# RP2350.net
KiCad netlist of a schematic drawn in Altium Designer
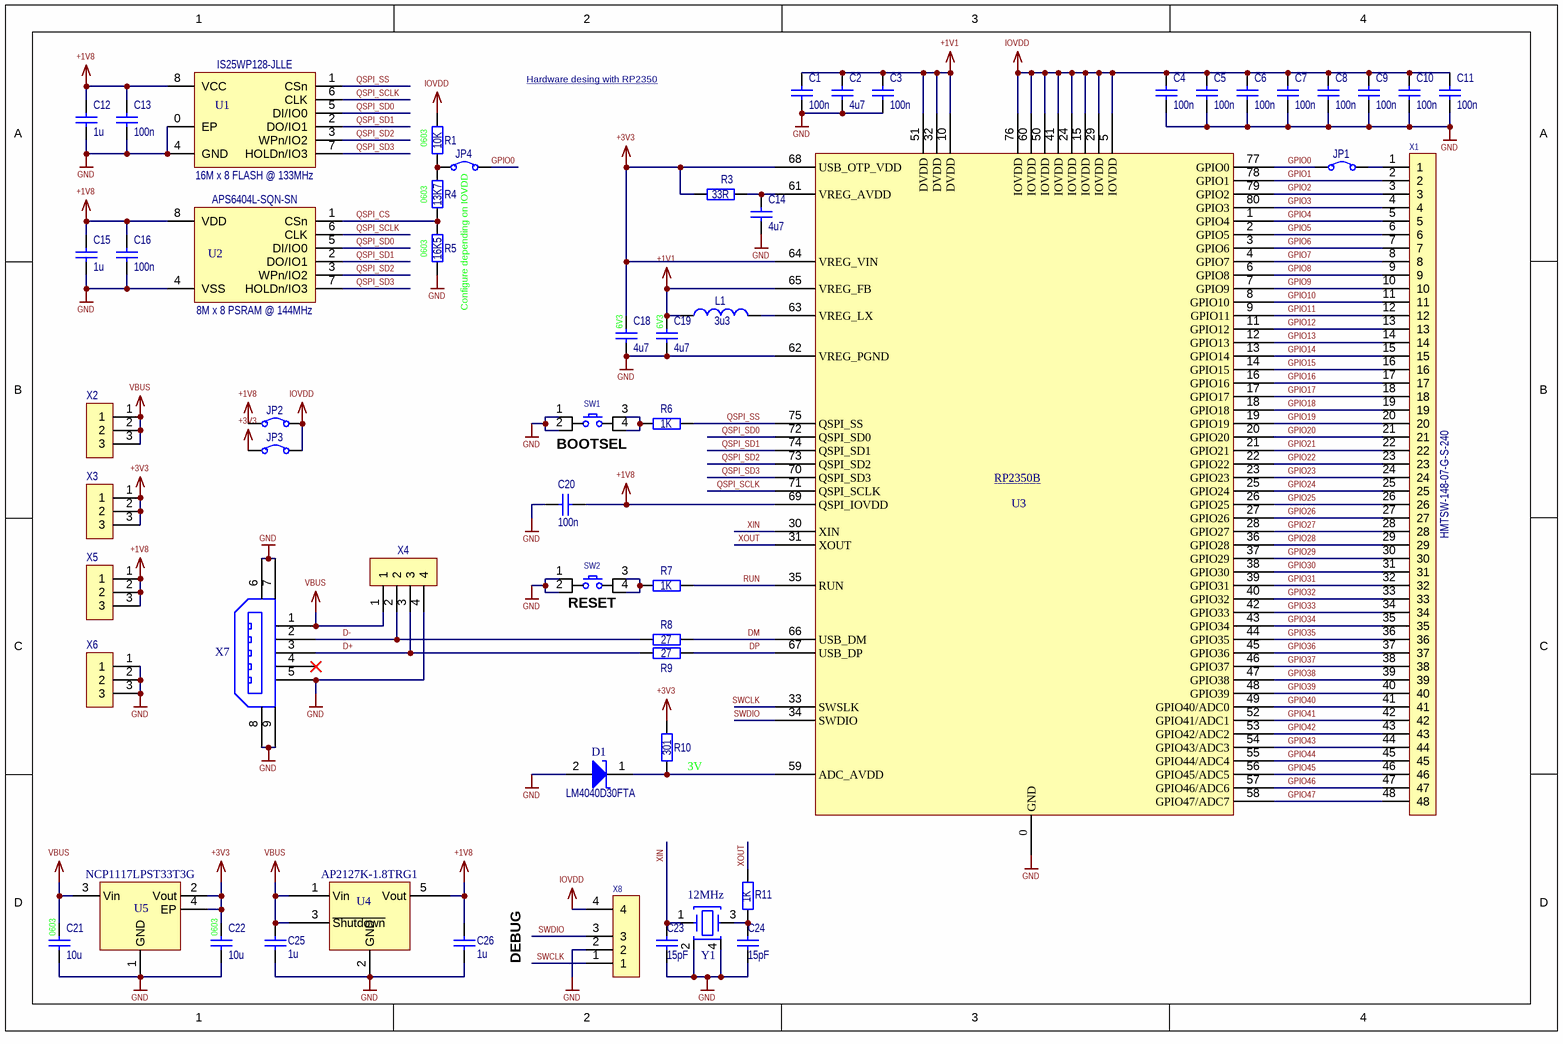
[diagram p0: RP2350.SchDoc]

(export (version "E")
  (design (tool "Eeschema 10.0.6"))
  (components
    (comp (ref "C1")
      (value "100n")
      (footprint "CAPC0402")
      (description "Capacitor; Ceramic; 100n; 2; 10V; X7R; 5%; -55°C ~ 125°C")
      (fields (field (name "Comment") "C0402C104J8RACTU"))
      (libsource (lib "Capacitors") (part "100n_0402_10V_X7R_5%"))
    )
    (comp (ref "C2")
      (value "4u7")
      (footprint "CAPC0402")
      (description "Capacitor; Ceramic; 4.7u; 0402; 10V; X5R; 10%; -55°C ~ 85°C")
      (fields
        (field (name "MANUFACTURER") "Samsung Electro-Mechanics")
        (field (name "MANUFACTURER PART NUMBER") "CL05A475KP5NRNC")
      )
      (libsource (lib "Capacitors") (part "4u7_0402_10V_X5R_10%"))
    )
    (comp (ref "C3")
      (value "100n")
      (footprint "CAPC0402")
      (description "Capacitor; Ceramic; 100n; 0402; 10V; X7R; 5%; -55°C ~ 125°C")
      (fields (field (name "Comment") "C0402C104J8RACTU"))
      (libsource (lib "Capacitors") (part "100n_0402_10V_X7R_5%"))
    )
    (comp (ref "C4")
      (value "100n")
      (footprint "CAPC0402")
      (description "Capacitor; Ceramic; 100n; 0402; 10V; X7R; 5%; -55°C ~ 125°C")
      (fields (field (name "Comment") "C0402C104J8RACTU"))
      (libsource (lib "Capacitors") (part "100n_0402_10V_X7R_5%"))
    )
    (comp (ref "C5")
      (value "100n")
      (footprint "CAPC0402")
      (description "Capacitor; Ceramic; 100n; 0402; 10V; X7R; 5%; -55°C ~ 125°C")
      (fields (field (name "Comment") "C0402C104J8RACTU"))
      (libsource (lib "Capacitors") (part "100n_0402_10V_X7R_5%"))
    )
    (comp (ref "C6")
      (value "100n")
      (footprint "CAPC0402")
      (description "Capacitor; Ceramic; 100n; 0402; 10V; X7R; 5%; -55°C ~ 125°C")
      (fields (field (name "Comment") "C0402C104J8RACTU"))
      (libsource (lib "Capacitors") (part "100n_0402_10V_X7R_5%"))
    )
    (comp (ref "C7")
      (value "100n")
      (footprint "CAPC0402")
      (description "Capacitor; Ceramic; 100n; 0402; 10V; X7R; 5%; -55°C ~ 125°C")
      (fields (field (name "Comment") "C0402C104J8RACTU"))
      (libsource (lib "Capacitors") (part "100n_0402_10V_X7R_5%"))
    )
    (comp (ref "C8")
      (value "100n")
      (footprint "CAPC0402")
      (description "Capacitor; Ceramic; 100n; 0402; 10V; X7R; 5%; -55°C ~ 125°C")
      (fields (field (name "Comment") "C0402C104J8RACTU"))
      (libsource (lib "Capacitors") (part "100n_0402_10V_X7R_5%"))
    )
    (comp (ref "C9")
      (value "100n")
      (footprint "CAPC0402")
      (description "Capacitor; Ceramic; 100n; 0402; 10V; X7R; 5%; -55°C ~ 125°C")
      (fields (field (name "Comment") "C0402C104J8RACTU"))
      (libsource (lib "Capacitors") (part "100n_0402_10V_X7R_5%"))
    )
    (comp (ref "C10")
      (value "100n")
      (footprint "CAPC0402")
      (description "Capacitor; Ceramic; 100n; 0402; 10V; X7R; 5%; -55°C ~ 125°C")
      (fields (field (name "Comment") "C0402C104J8RACTU"))
      (libsource (lib "Capacitors") (part "100n_0402_10V_X7R_5%"))
    )
    (comp (ref "C11")
      (value "100n")
      (footprint "CAPC0402")
      (description "Capacitor; Ceramic; 100n; 0402; 10V; X7R; 5%; -55°C ~ 125°C")
      (fields (field (name "Comment") "C0402C104J8RACTU"))
      (libsource (lib "Capacitors") (part "100n_0402_10V_X7R_5%"))
    )
    (comp (ref "C12")
      (value "1u")
      (footprint "CAPC0402")
      (description "Capacitor; Ceramic; 1u; 0402; 10V; X5R; 10%; -55°C ~ 85°C")
      (fields
        (field (name "MANUFACTURER") "Samsung Electro-Mechanics")
        (field (name "MANUFACTURER PART NUMBER") "CL05A105KP5NNNC")
      )
      (libsource (lib "Capacitors") (part "1u_0402_10V_X5R_10%"))
    )
    (comp (ref "C13")
      (value "100n")
      (footprint "CAPC0402")
      (description "Capacitor; Ceramic; 100n; 0402; 10V; X7R; 5%; -55°C ~ 125°C")
      (fields (field (name "Comment") "C0402C104J8RACTU"))
      (libsource (lib "Capacitors") (part "100n_0402_10V_X7R_5%"))
    )
    (comp (ref "C14")
      (value "4u7")
      (footprint "CAPC0402")
      (description "Capacitor; Ceramic; 4.7u; 0402; 10V; X5R; 10%; -55°C ~ 85°C")
      (fields
        (field (name "MANUFACTURER") "Samsung Electro-Mechanics")
        (field (name "MANUFACTURER PART NUMBER") "CL05A475KP5NRNC")
      )
      (libsource (lib "Capacitors") (part "4u7_0402_10V_X5R_10%"))
    )
    (comp (ref "C15")
      (value "1u")
      (footprint "CAPC0402")
      (description "Capacitor; Ceramic; 1u; 0402; 10V; X5R; 10%; -55°C ~ 85°C")
      (fields
        (field (name "MANUFACTURER") "Samsung Electro-Mechanics")
        (field (name "MANUFACTURER PART NUMBER") "CL05A105KP5NNNC")
      )
      (libsource (lib "Capacitors") (part "1u_0402_10V_X5R_10%"))
    )
    (comp (ref "C16")
      (value "100n")
      (footprint "CAPC0402")
      (description "Capacitor; Ceramic; 100n; 0402; 10V; X7R; 5%; -55°C ~ 125°C")
      (fields (field (name "Comment") "C0402C104J8RACTU"))
      (libsource (lib "Capacitors") (part "100n_0402_10V_X7R_5%"))
    )
    (comp (ref "C18")
      (value "6V3")
      (footprint "CAPC0603")
      (description "Capacitor; Ceramic; 4.7u; 0603; 6.3V; X7S; 10%; -55°C ~ 125°C")
      (fields
        (field (name "MANUFACTURER") "Murata Electronics")
        (field (name "MANUFACTURER PART NUMBER") "GCJ188C70J475KE02D")
        (field (name "ALTIUM_VALUE") "4u7")
      )
      (libsource (lib "symbols") (part "4u7_0603_6V3_X7S_10%"))
    )
    (comp (ref "C19")
      (value "6V3")
      (footprint "CAPC0603")
      (description "Capacitor; Ceramic; 4.7u; 0603; 6.3V; X7S; 10%; -55°C ~ 125°C")
      (fields
        (field (name "MANUFACTURER") "Murata Electronics")
        (field (name "MANUFACTURER PART NUMBER") "GCJ188C70J475KE02D")
        (field (name "ALTIUM_VALUE") "4u7")
      )
      (libsource (lib "symbols") (part "4u7_0603_6V3_X7S_10%"))
    )
    (comp (ref "C20")
      (value "100n")
      (footprint "CAPC0402")
      (description "Capacitor; Ceramic; 100n; 0402; 10V; X7R; 5%; -55°C ~ 125°C")
      (fields (field (name "Comment") "C0402C104J8RACTU"))
      (libsource (lib "Capacitors") (part "100n_0402_10V_X7R_5%"))
    )
    (comp (ref "C21")
      (value "0603")
      (footprint "CAPC0603")
      (description "Capacitor; Ceramic; 10u; 0603; 16V; X5R; 10%; -55°C ~ 85°C")
      (fields (field (name "ALTIUM_VALUE") "10u"))
      (libsource (lib "Capacitors") (part "10u_0603_16V_X5R_10%"))
    )
    (comp (ref "C22")
      (value "0603")
      (footprint "CAPC0603")
      (description "Capacitor; Ceramic; 10u; 0603; 16V; X5R; 10%; -55°C ~ 85°C")
      (fields (field (name "ALTIUM_VALUE") "10u"))
      (libsource (lib "Capacitors") (part "10u_0603_16V_X5R_10%"))
    )
    (comp (ref "C23")
      (value "15pF")
      (footprint "CAPC0402")
      (description "Capacitor; Ceramic; 15p; 0402; 25V; C0G/NP0; +/-5%; -55°C ~ 125°C")
      (fields
        (field (name "MANUFACTURER") "YAGEO")
        (field (name "MANUFACTURER PART NUMBER") "CC0402JRNPO8BN150")
      )
      (libsource (lib "symbols") (part "15p_0402_25V_C0G/NP0_5%"))
    )
    (comp (ref "C24")
      (value "15pF")
      (footprint "CAPC0402")
      (description "Capacitor; Ceramic; 15p; 0402; 25V; C0G/NP0; +/-5%; -55°C ~ 125°C")
      (fields
        (field (name "MANUFACTURER") "YAGEO")
        (field (name "MANUFACTURER PART NUMBER") "CC0402JRNPO8BN150")
      )
      (libsource (lib "symbols") (part "15p_0402_25V_C0G/NP0_5%"))
    )
    (comp (ref "C25")
      (value "1u")
      (footprint "CAPC0402")
      (description "Capacitor; Ceramic; 1u; 0402; 10V; X5R; 10%; -55°C ~ 85°C")
      (fields
        (field (name "MANUFACTURER") "Samsung Electro-Mechanics")
        (field (name "MANUFACTURER PART NUMBER") "CL05A105KP5NNNC")
      )
      (libsource (lib "Capacitors") (part "1u_0402_10V_X5R_10%"))
    )
    (comp (ref "C26")
      (value "1u")
      (footprint "CAPC0402")
      (description "Capacitor; Ceramic; 1u; 0402; 10V; X5R; 10%; -55°C ~ 85°C")
      (fields
        (field (name "MANUFACTURER") "Samsung Electro-Mechanics")
        (field (name "MANUFACTURER PART NUMBER") "CL05A105KP5NNNC")
      )
      (libsource (lib "Capacitors") (part "1u_0402_10V_X5R_10%"))
    )
    (comp (ref "D1")
      (value "LM4040D30FTA")
      (footprint "SOT23-3")
      (description "Shunt Voltage Reference IC Fixed 3V ±1% 15 mA SOT-23-3")
      (fields (field (name "MANUFACTURER") "Diodes Incorporated") (field (name "ALTIUM_VALUE") "3V"))
      (libsource (lib "symbols") (part "LM4040D30FTA"))
    )
    (comp (ref "JP1")
      (value "5110 Keystone")
      (footprint "JumperSMD_0603")
      (description "Jumper; Chip; 0R; 0603; 500mW")
      (fields (field (name "MANUFACTURER") "Keystone") (field (name "MANUFACTURER PART NUMBER") "5110"))
      (libsource (lib "Jumpers") (part "JMP_0R_0603"))
    )
    (comp (ref "JP2")
      (value "5110 Keystone")
      (footprint "JumperSMD_0603")
      (description "Jumper; Chip; 0R; 0603; 500mW")
      (fields (field (name "MANUFACTURER") "Keystone") (field (name "MANUFACTURER PART NUMBER") "5110"))
      (libsource (lib "Jumpers") (part "JMP_0R_0603"))
    )
    (comp (ref "JP3")
      (value "5110 Keystone")
      (footprint "JumperSMD_0603")
      (description "Jumper; Chip; 0R; 0603; 500mW")
      (fields (field (name "MANUFACTURER") "Keystone") (field (name "MANUFACTURER PART NUMBER") "5110"))
      (libsource (lib "Jumpers") (part "JMP_0R_0603"))
    )
    (comp (ref "JP4")
      (value "5110 Keystone")
      (footprint "JumperSMD_0603")
      (description "Jumper; Chip; 0R; 0603; 500mW")
      (fields (field (name "MANUFACTURER") "Keystone") (field (name "MANUFACTURER PART NUMBER") "5110"))
      (libsource (lib "Jumpers") (part "JMP_0R_0603"))
    )
    (comp (ref "L1")
      (value "3u3")
      (footprint "IND_0806")
      (description "3.3 µH Shielded Inductor 1.4 A 225mOhm Max 0806")
      (fields
        (field (name "MANUFACTURER") "Bourns Inc.")
        (field (name "MANUFACTURER PART NUMBER") "SRP2010DPA-3R3M")
      )
      (libsource (lib "Inductances") (part "IND_3u3_2X1.6mm_1.4A_20%"))
    )
    (comp (ref "R1")
      (value "0603")
      (footprint "RESC0603")
      (description "Resistor; Chip; 10k; 0603; 75V; 1%; 100ppm; 100mW; -55°C ~ 155°C")
      (fields (field (name "ALTIUM_VALUE") "10K"))
      (libsource (lib "Resistors") (part "10K_0603_100mW_1%_100ppm"))
    )
    (comp (ref "R3")
      (value "33R")
      (footprint "RESC0402")
      (description "Resistor; Chip; 33R; 0402; 50V; 1%; 100ppm; 63mW; -55°C ~ 155°C")
      (fields
        (field (name "MANUFACTURER") "Yageo")
        (field (name "MANUFACTURER PART NUMBER") "RC0402FR-0733RL")
      )
      (libsource (lib "Resistors") (part "33R_0402_63mW_1%_100ppm"))
    )
    (comp (ref "R4")
      (value "0603")
      (footprint "RESC0603")
      (description "Resistor; Chip; 13K7; 0603; 0.1%; 25ppm; 100mW; -55°C ~ 155°C")
      (fields
        (field (name "MANUFACTURER") "YAGEO")
        (field (name "MANUFACTURER PART NUMBER") "RT0603BRD0713K7L")
        (field (name "ALTIUM_VALUE") "13K7")
      )
      (libsource (lib "symbols") (part "13K7_0603_100mW_0.1%_25ppm"))
    )
    (comp (ref "R5")
      (value "0603")
      (footprint "RESC0603")
      (description "Resistor; Chip; 16K5; 0603; 0.1%; 25ppm; 100mW; -55°C ~ 155°C")
      (fields
        (field (name "MANUFACTURER") "YAGEO")
        (field (name "MANUFACTURER PART NUMBER") "RT0603BRD0716K5L")
        (field (name "ALTIUM_VALUE") "16K5")
      )
      (libsource (lib "symbols") (part "16K5_0603_100mW_0.1%_25ppm"))
    )
    (comp (ref "R6")
      (value "1K")
      (footprint "RESC0402")
      (description "Resistor; Chip; 1k; 0402; 50V; 1%; 100ppm; 63mW; -55°C ~ 155°C")
      (fields
        (field (name "MANUFACTURER") "Yageo")
        (field (name "MANUFACTURER PART NUMBER") "RC0402FR-071KL")
      )
      (libsource (lib "") (part "1K_0402_63mW_1%_100ppm_1"))
    )
    (comp (ref "R7")
      (value "1K")
      (footprint "RESC0402")
      (description "Resistor; Chip; 1k; 0402; 50V; 1%; 100ppm; 63mW; -55°C ~ 155°C")
      (fields
        (field (name "MANUFACTURER") "Yageo")
        (field (name "MANUFACTURER PART NUMBER") "RC0402FR-071KL")
      )
      (libsource (lib "") (part "1K_0402_63mW_1%_100ppm_1"))
    )
    (comp (ref "R8")
      (value "27")
      (footprint "RESC0402")
      (description "Resistor; Chip; 27Ohm; 0402; 1%; 100ppm; 63mW; -55°C ~ 155°C")
      (fields
        (field (name "MANUFACTURER") "YAGEO")
        (field (name "MANUFACTURER PART NUMBER") "RC0402FR-0727RL")
      )
      (libsource (lib "symbols") (part "27R_0402_63mW_1%_100ppm"))
    )
    (comp (ref "R9")
      (value "27")
      (footprint "RESC0402")
      (description "Resistor; Chip; 27Ohm; 0402; 1%; 100ppm; 63mW; -55°C ~ 155°C")
      (fields
        (field (name "MANUFACTURER") "YAGEO")
        (field (name "MANUFACTURER PART NUMBER") "RC0402FR-0727RL")
      )
      (libsource (lib "symbols") (part "27R_0402_63mW_1%_100ppm"))
    )
    (comp (ref "R10")
      (value "301")
      (footprint "RESC0402")
      (description "Resistor; Chip; 301R; 0402; 1%; 100ppm; 63mW; -55°C ~ 155°C")
      (fields
        (field (name "MANUFACTURER") "YAGEO")
        (field (name "MANUFACTURER PART NUMBER") "RC0402FR-07301RL")
      )
      (libsource (lib "symbols") (part "301R_0402_63mW_1%_100ppm"))
    )
    (comp (ref "R11")
      (value "1K")
      (footprint "RESC0402")
      (description "Resistor; Chip; 1k; 0402; 50V; 1%; 100ppm; 63mW; -55°C ~ 155°C")
      (fields
        (field (name "MANUFACTURER") "Yageo")
        (field (name "MANUFACTURER PART NUMBER") "RC0402FR-071KL")
      )
      (libsource (lib "Resistors") (part "1K_0402_63mW_1%_100ppm"))
    )
    (comp (ref "SW1")
      (value "434133025816")
      (footprint "434133025816")
      (description "SWITCH TACTILE SPST-NO 0.05A 16V")
      (fields (field (name "MANUFACTURER") "Würth Elektronik"))
      (libsource (lib "symbols") (part "434133025816"))
    )
    (comp (ref "SW2")
      (value "434133025816")
      (footprint "434133025816")
      (description "SWITCH TACTILE SPST-NO 0.05A 16V")
      (fields (field (name "MANUFACTURER") "Würth Elektronik"))
      (libsource (lib "symbols") (part "434133025816"))
    )
    (comp (ref "U1")
      (value "16M x 8 FLASH @ 133MHz")
      (footprint "WSON8-6x8")
      (description "IC FLASH 128MBIT SPI/QUAD 8WSON")
      (fields
        (field (name "MANUFACTURER") "ISSI, Integrated Silicon Solution Inc")
        (field (name "MANUFACTURER PART NUMBER") "IS25WP128-JLLE")
        (field (name "Comment") "IS25WP128-JLLE")
      )
      (libsource (lib "symbols") (part "IS25WP128-JLLE"))
    )
    (comp (ref "U2")
      (value "8M x 8 PSRAM @ 144MHz")
      (footprint "SOP-8L (150)")
      (description "IC PSRAM 64MBIT QSPI SOP-8L")
      (fields
        (field (name "MANUFACTURER") "AP Memory")
        (field (name "MANUFACTURER PART NUMBER") "APS6404L-SQN-SN")
        (field (name "Comment") "APS6404L-SQN-SN")
      )
      (libsource (lib "symbols") (part "APS6404L-SQN-SN"))
    )
    (comp (ref "U3")
      (value "RP2350B")
      (footprint "QFN-80")
      (description "IC MCU 32BIT EXT MEM 80QFN")
      (libsource (lib "symbols") (part "RP2350B"))
    )
    (comp (ref "U4")
      (value "AP2127K-1.8TRG1")
      (footprint "SOT23-5")
      (description "IC REG LINEAR 1.8V 300MA SOT23-5")
      (fields
        (field (name "MANUFACTURER") "Diodes Incorporated")
        (field (name "MANUFACTURER PART NUMBER") "AP2127K-1.8TRG1")
      )
      (libsource (lib "symbols") (part "AP2127K-1.8TRG1"))
    )
    (comp (ref "U5")
      (value "NCP1117LPST33T3G")
      (footprint "SOT-232-4")
      (description "IC REG LINEAR 3.3V 1A SOT223")
      (fields (field (name "MANUFACTURER") "onsemi"))
      (libsource (lib "symbols") (part "NCP1117LPST33T3G"))
    )
    (comp (ref "X1")
      (value "HMTSW-148-07-G-S-240")
      (footprint "HDR_TH_1X48_M_00")
      (description "Header; 1x48 pins; Male; Straight; Pitch 2.54mm; Samtec HMTSW Series")
      (libsource (lib "symbols") (part "HDR_TH_1X48_M_00"))
    )
    (comp (ref "X2")
      (value "825433-3")
      (footprint "HDR_TH_1X3_M_00")
      (description "Header; 1x3 pins; Male; Straight; Pitch 2.54mm")
      (fields
        (field (name "MANUFACTURER") "TE Connectivity")
        (field (name "MANUFACTURER PART NUMBER") "825433-2")
      )
      (libsource (lib "Connections") (part "HDR_TH_1X3_M_00"))
    )
    (comp (ref "X3")
      (value "825433-3")
      (footprint "HDR_TH_1X3_M_00")
      (description "Header; 1x3 pins; Male; Straight; Pitch 2.54mm")
      (fields
        (field (name "MANUFACTURER") "TE Connectivity")
        (field (name "MANUFACTURER PART NUMBER") "825433-2")
      )
      (libsource (lib "Connections") (part "HDR_TH_1X3_M_00"))
    )
    (comp (ref "X4")
      (value "HMTSW-104-07-G-S-240")
      (footprint "HDR_TH_1X4_M_00")
      (description "Header; 1x4 pins; Male; Straight; Pitch 2.54mm; Samtec HMTSW Series")
      (libsource (lib "symbols") (part "HDR_TH_1X4_M_00"))
    )
    (comp (ref "X5")
      (value "825433-3")
      (footprint "HDR_TH_1X3_M_00")
      (description "Header; 1x3 pins; Male; Straight; Pitch 2.54mm")
      (fields
        (field (name "MANUFACTURER") "TE Connectivity")
        (field (name "MANUFACTURER PART NUMBER") "825433-2")
      )
      (libsource (lib "Connections") (part "HDR_TH_1X3_M_00"))
    )
    (comp (ref "X6")
      (value "825433-3")
      (footprint "HDR_TH_1X3_M_00")
      (description "Header; 1x3 pins; Male; Straight; Pitch 2.54mm")
      (fields
        (field (name "MANUFACTURER") "TE Connectivity")
        (field (name "MANUFACTURER PART NUMBER") "825433-2")
      )
      (libsource (lib "Connections") (part "HDR_TH_1X3_M_00"))
    )
    (comp (ref "X7")
      (value "1734327-1")
      (footprint "1734327-1")
      (description "USB - mini A USB 2.0 Receptacle Connector 5 Position Surface Mount, Right Angle")
      (fields (field (name "MANUFACTURER") "TE Connectivity AMP Connectors"))
      (libsource (lib "symbols") (part "1734327-1"))
    )
    (comp (ref "X8")
      (value "HMTSW-106-07-G-S-240")
      (footprint "HDR_TH_1X3+0+1_M_00")
      (description "Header; 1x5 pins (with key); Male; Straight; Pitch 2.54mm; Samtec HMTSW Series")
      (fields
        (field (name "MANUFACTURER") "Samtec Inc.")
        (field (name "MANUFACTURER PART NUMBER") "HMTSW-105-07-G-S-240")
      )
      (libsource (lib "symbols") (part "HDR_TH_1X3+1_M_00"))
    )
    (comp (ref "Y1")
      (value "12MHz")
      (footprint "ABM8")
      (description "Christal; SMD; 12 MHz ±30ppm; 10pF/50Ohm")
      (fields
        (field (name "MANUFACTURER") "Abracon LLC")
        (field (name "MANUFACTURER PART NUMBER") "ABM8-272-T3")
      )
      (libsource (lib "symbols") (part "ABM8-272-T3"))
    )
  )
  (nets
    (net (code "1") (name "+1V1") (class "Default")
      (node (ref "C1") (pin "2") (pinfunction "2_2") (pintype "passive"))
      (node (ref "C19") (pin "2") (pinfunction "2_2") (pintype "passive"))
      (node (ref "C2") (pin "2") (pinfunction "2_2") (pintype "passive"))
      (node (ref "C3") (pin "2") (pinfunction "2_2") (pintype "passive"))
      (node (ref "L1") (pin "1") (pinfunction "1_1") (pintype "passive"))
      (node (ref "U3") (pin "10") (pinfunction "DVDD_10") (pintype "passive"))
      (node (ref "U3") (pin "32") (pinfunction "DVDD_32") (pintype "passive"))
      (node (ref "U3") (pin "51") (pinfunction "DVDD_51") (pintype "passive"))
      (node (ref "U3") (pin "65") (pinfunction "VREG_FB_65") (pintype "passive"))
    )
    (net (code "2") (name "+1V8") (class "Default")
      (node (ref "C12") (pin "1") (pinfunction "1_1") (pintype "passive"))
      (node (ref "C13") (pin "2") (pinfunction "2_2") (pintype "passive"))
      (node (ref "C15") (pin "1") (pinfunction "1_1") (pintype "passive"))
      (node (ref "C16") (pin "2") (pinfunction "2_2") (pintype "passive"))
      (node (ref "C20") (pin "2") (pinfunction "2_2") (pintype "passive"))
      (node (ref "C26") (pin "1") (pinfunction "1_1") (pintype "passive"))
      (node (ref "JP2") (pin "1") (pinfunction "1_1") (pintype "passive"))
      (node (ref "U1") (pin "8") (pinfunction "VCC_8") (pintype "passive"))
      (node (ref "U2") (pin "8") (pinfunction "VDD_8") (pintype "passive"))
      (node (ref "U3") (pin "69") (pinfunction "QSPI_IOVDD_69") (pintype "passive"))
      (node (ref "U4") (pin "5") (pinfunction "Vout_5") (pintype "passive"))
      (node (ref "X5") (pin "1") (pinfunction "1_1") (pintype "passive"))
      (node (ref "X5") (pin "2") (pinfunction "2_2") (pintype "passive"))
      (node (ref "X5") (pin "3") (pinfunction "3_3") (pintype "passive"))
    )
    (net (code "3") (name "+3V3") (class "Default")
      (node (ref "C18") (pin "2") (pinfunction "2_2") (pintype "passive"))
      (node (ref "C22") (pin "2") (pinfunction "2_2") (pintype "passive"))
      (node (ref "JP3") (pin "1") (pinfunction "1_1") (pintype "passive"))
      (node (ref "R10") (pin "2") (pinfunction "2_2") (pintype "passive"))
      (node (ref "R3") (pin "1") (pinfunction "1_1") (pintype "passive"))
      (node (ref "U3") (pin "64") (pinfunction "VREG_VIN_64") (pintype "passive"))
      (node (ref "U3") (pin "68") (pinfunction "USB_OTP_VDD_68") (pintype "passive"))
      (node (ref "U5") (pin "2") (pinfunction "Vout_2") (pintype "passive"))
      (node (ref "U5") (pin "4") (pinfunction "EP_4") (pintype "passive"))
      (node (ref "X3") (pin "1") (pinfunction "1_1") (pintype "passive"))
      (node (ref "X3") (pin "2") (pinfunction "2_2") (pintype "passive"))
      (node (ref "X3") (pin "3") (pinfunction "3_3") (pintype "passive"))
    )
    (net (code "4") (name "/D+") (class "Default")
      (node (ref "R9") (pin "1") (pinfunction "1_1") (pintype "passive"))
      (node (ref "X4") (pin "3") (pinfunction "3_3") (pintype "passive"))
      (node (ref "X7") (pin "3") (pinfunction "3_3") (pintype "passive"))
    )
    (net (code "5") (name "/D-") (class "Default")
      (node (ref "R8") (pin "1") (pinfunction "1_1") (pintype "passive"))
      (node (ref "X4") (pin "2") (pinfunction "2_2") (pintype "passive"))
      (node (ref "X7") (pin "2") (pinfunction "2_2") (pintype "passive"))
    )
    (net (code "6") (name "/DM") (class "Default")
      (node (ref "R8") (pin "2") (pinfunction "2_2") (pintype "passive"))
      (node (ref "U3") (pin "66") (pinfunction "USB_DM_66") (pintype "passive"))
    )
    (net (code "7") (name "/DP") (class "Default")
      (node (ref "R9") (pin "2") (pinfunction "2_2") (pintype "passive"))
      (node (ref "U3") (pin "67") (pinfunction "USB_DP_67") (pintype "passive"))
    )
    (net (code "8") (name "/GPIO0") (class "Default")
      (node (ref "JP1") (pin "1") (pinfunction "1_1") (pintype "passive"))
      (node (ref "JP4") (pin "2") (pinfunction "2_2") (pintype "passive"))
      (node (ref "U3") (pin "77") (pinfunction "GPIO0_77") (pintype "passive"))
    )
    (net (code "9") (name "/GPIO1") (class "Default")
      (node (ref "U3") (pin "78") (pinfunction "GPIO1_78") (pintype "passive"))
      (node (ref "X1") (pin "2") (pinfunction "2_2") (pintype "passive"))
    )
    (net (code "10") (name "/GPIO2") (class "Default")
      (node (ref "U3") (pin "79") (pinfunction "GPIO2_79") (pintype "passive"))
      (node (ref "X1") (pin "3") (pinfunction "3_3") (pintype "passive"))
    )
    (net (code "11") (name "/GPIO3") (class "Default")
      (node (ref "U3") (pin "80") (pinfunction "GPIO3_80") (pintype "passive"))
      (node (ref "X1") (pin "4") (pinfunction "4_4") (pintype "passive"))
    )
    (net (code "12") (name "/GPIO4") (class "Default")
      (node (ref "U3") (pin "1") (pinfunction "GPIO4_1") (pintype "passive"))
      (node (ref "X1") (pin "5") (pinfunction "5_5") (pintype "passive"))
    )
    (net (code "13") (name "/GPIO5") (class "Default")
      (node (ref "U3") (pin "2") (pinfunction "GPIO5_2") (pintype "passive"))
      (node (ref "X1") (pin "6") (pinfunction "6_6") (pintype "passive"))
    )
    (net (code "14") (name "/GPIO6") (class "Default")
      (node (ref "U3") (pin "3") (pinfunction "GPIO6_3") (pintype "passive"))
      (node (ref "X1") (pin "7") (pinfunction "7_7") (pintype "passive"))
    )
    (net (code "15") (name "/GPIO7") (class "Default")
      (node (ref "U3") (pin "4") (pinfunction "GPIO7_4") (pintype "passive"))
      (node (ref "X1") (pin "8") (pinfunction "8_8") (pintype "passive"))
    )
    (net (code "16") (name "/GPIO8") (class "Default")
      (node (ref "U3") (pin "6") (pinfunction "GPIO8_6") (pintype "passive"))
      (node (ref "X1") (pin "9") (pinfunction "9_9") (pintype "passive"))
    )
    (net (code "17") (name "/GPIO9") (class "Default")
      (node (ref "U3") (pin "7") (pinfunction "GPIO9_7") (pintype "passive"))
      (node (ref "X1") (pin "10") (pinfunction "10_10") (pintype "passive"))
    )
    (net (code "18") (name "/GPIO10") (class "Default")
      (node (ref "U3") (pin "8") (pinfunction "GPIO10_8") (pintype "passive"))
      (node (ref "X1") (pin "11") (pinfunction "11_11") (pintype "passive"))
    )
    (net (code "19") (name "/GPIO11") (class "Default")
      (node (ref "U3") (pin "9") (pinfunction "GPIO11_9") (pintype "passive"))
      (node (ref "X1") (pin "12") (pinfunction "12_12") (pintype "passive"))
    )
    (net (code "20") (name "/GPIO12") (class "Default")
      (node (ref "U3") (pin "11") (pinfunction "GPIO12_11") (pintype "passive"))
      (node (ref "X1") (pin "13") (pinfunction "13_13") (pintype "passive"))
    )
    (net (code "21") (name "/GPIO13") (class "Default")
      (node (ref "U3") (pin "12") (pinfunction "GPIO13_12") (pintype "passive"))
      (node (ref "X1") (pin "14") (pinfunction "14_14") (pintype "passive"))
    )
    (net (code "22") (name "/GPIO14") (class "Default")
      (node (ref "U3") (pin "13") (pinfunction "GPIO14_13") (pintype "passive"))
      (node (ref "X1") (pin "15") (pinfunction "15_15") (pintype "passive"))
    )
    (net (code "23") (name "/GPIO15") (class "Default")
      (node (ref "U3") (pin "14") (pinfunction "GPIO15_14") (pintype "passive"))
      (node (ref "X1") (pin "16") (pinfunction "16_16") (pintype "passive"))
    )
    (net (code "24") (name "/GPIO16") (class "Default")
      (node (ref "U3") (pin "16") (pinfunction "GPIO16_16") (pintype "passive"))
      (node (ref "X1") (pin "17") (pinfunction "17_17") (pintype "passive"))
    )
    (net (code "25") (name "/GPIO17") (class "Default")
      (node (ref "U3") (pin "17") (pinfunction "GPIO17_17") (pintype "passive"))
      (node (ref "X1") (pin "18") (pinfunction "18_18") (pintype "passive"))
    )
    (net (code "26") (name "/GPIO18") (class "Default")
      (node (ref "U3") (pin "18") (pinfunction "GPIO18_18") (pintype "passive"))
      (node (ref "X1") (pin "19") (pinfunction "19_19") (pintype "passive"))
    )
    (net (code "27") (name "/GPIO19") (class "Default")
      (node (ref "U3") (pin "19") (pinfunction "GPIO19_19") (pintype "passive"))
      (node (ref "X1") (pin "20") (pinfunction "20_20") (pintype "passive"))
    )
    (net (code "28") (name "/GPIO20") (class "Default")
      (node (ref "U3") (pin "20") (pinfunction "GPIO20_20") (pintype "passive"))
      (node (ref "X1") (pin "21") (pinfunction "21_21") (pintype "passive"))
    )
    (net (code "29") (name "/GPIO21") (class "Default")
      (node (ref "U3") (pin "21") (pinfunction "GPIO21_21") (pintype "passive"))
      (node (ref "X1") (pin "22") (pinfunction "22_22") (pintype "passive"))
    )
    (net (code "30") (name "/GPIO22") (class "Default")
      (node (ref "U3") (pin "22") (pinfunction "GPIO22_22") (pintype "passive"))
      (node (ref "X1") (pin "23") (pinfunction "23_23") (pintype "passive"))
    )
    (net (code "31") (name "/GPIO23") (class "Default")
      (node (ref "U3") (pin "23") (pinfunction "GPIO23_23") (pintype "passive"))
      (node (ref "X1") (pin "24") (pinfunction "24_24") (pintype "passive"))
    )
    (net (code "32") (name "/GPIO24") (class "Default")
      (node (ref "U3") (pin "25") (pinfunction "GPIO24_25") (pintype "passive"))
      (node (ref "X1") (pin "25") (pinfunction "25_25") (pintype "passive"))
    )
    (net (code "33") (name "/GPIO25") (class "Default")
      (node (ref "U3") (pin "26") (pinfunction "GPIO25_26") (pintype "passive"))
      (node (ref "X1") (pin "26") (pinfunction "26_26") (pintype "passive"))
    )
    (net (code "34") (name "/GPIO26") (class "Default")
      (node (ref "U3") (pin "27") (pinfunction "GPIO26_27") (pintype "passive"))
      (node (ref "X1") (pin "27") (pinfunction "27_27") (pintype "passive"))
    )
    (net (code "35") (name "/GPIO27") (class "Default")
      (node (ref "U3") (pin "28") (pinfunction "GPIO27_28") (pintype "passive"))
      (node (ref "X1") (pin "28") (pinfunction "28_28") (pintype "passive"))
    )
    (net (code "36") (name "/GPIO28") (class "Default")
      (node (ref "U3") (pin "36") (pinfunction "GPIO28_36") (pintype "passive"))
      (node (ref "X1") (pin "29") (pinfunction "29_29") (pintype "passive"))
    )
    (net (code "37") (name "/GPIO29") (class "Default")
      (node (ref "U3") (pin "37") (pinfunction "GPIO29_37") (pintype "passive"))
      (node (ref "X1") (pin "30") (pinfunction "30_30") (pintype "passive"))
    )
    (net (code "38") (name "/GPIO30") (class "Default")
      (node (ref "U3") (pin "38") (pinfunction "GPIO30_38") (pintype "passive"))
      (node (ref "X1") (pin "31") (pinfunction "31_31") (pintype "passive"))
    )
    (net (code "39") (name "/GPIO31") (class "Default")
      (node (ref "U3") (pin "39") (pinfunction "GPIO31_39") (pintype "passive"))
      (node (ref "X1") (pin "32") (pinfunction "32_32") (pintype "passive"))
    )
    (net (code "40") (name "/GPIO32") (class "Default")
      (node (ref "U3") (pin "40") (pinfunction "GPIO32_40") (pintype "passive"))
      (node (ref "X1") (pin "33") (pinfunction "33_33") (pintype "passive"))
    )
    (net (code "41") (name "/GPIO33") (class "Default")
      (node (ref "U3") (pin "42") (pinfunction "GPIO33_42") (pintype "passive"))
      (node (ref "X1") (pin "34") (pinfunction "34_34") (pintype "passive"))
    )
    (net (code "42") (name "/GPIO34") (class "Default")
      (node (ref "U3") (pin "43") (pinfunction "GPIO34_43") (pintype "passive"))
      (node (ref "X1") (pin "35") (pinfunction "35_35") (pintype "passive"))
    )
    (net (code "43") (name "/GPIO35") (class "Default")
      (node (ref "U3") (pin "44") (pinfunction "GPIO35_44") (pintype "passive"))
      (node (ref "X1") (pin "36") (pinfunction "36_36") (pintype "passive"))
    )
    (net (code "44") (name "/GPIO36") (class "Default")
      (node (ref "U3") (pin "45") (pinfunction "GPIO36_45") (pintype "passive"))
      (node (ref "X1") (pin "37") (pinfunction "37_37") (pintype "passive"))
    )
    (net (code "45") (name "/GPIO37") (class "Default")
      (node (ref "U3") (pin "46") (pinfunction "GPIO37_46") (pintype "passive"))
      (node (ref "X1") (pin "38") (pinfunction "38_38") (pintype "passive"))
    )
    (net (code "46") (name "/GPIO38") (class "Default")
      (node (ref "U3") (pin "47") (pinfunction "GPIO38_47") (pintype "passive"))
      (node (ref "X1") (pin "39") (pinfunction "39_39") (pintype "passive"))
    )
    (net (code "47") (name "/GPIO39") (class "Default")
      (node (ref "U3") (pin "48") (pinfunction "GPIO39_48") (pintype "passive"))
      (node (ref "X1") (pin "40") (pinfunction "40_40") (pintype "passive"))
    )
    (net (code "48") (name "/GPIO40") (class "Default")
      (node (ref "U3") (pin "49") (pinfunction "GPIO40/ADC0_49") (pintype "passive"))
      (node (ref "X1") (pin "41") (pinfunction "41_41") (pintype "passive"))
    )
    (net (code "49") (name "/GPIO41") (class "Default")
      (node (ref "U3") (pin "52") (pinfunction "GPIO41/ADC1_52") (pintype "passive"))
      (node (ref "X1") (pin "42") (pinfunction "42_42") (pintype "passive"))
    )
    (net (code "50") (name "/GPIO42") (class "Default")
      (node (ref "U3") (pin "53") (pinfunction "GPIO42/ADC2_53") (pintype "passive"))
      (node (ref "X1") (pin "43") (pinfunction "43_43") (pintype "passive"))
    )
    (net (code "51") (name "/GPIO43") (class "Default")
      (node (ref "U3") (pin "54") (pinfunction "GPIO43/ADC3_54") (pintype "passive"))
      (node (ref "X1") (pin "44") (pinfunction "44_44") (pintype "passive"))
    )
    (net (code "52") (name "/GPIO44") (class "Default")
      (node (ref "U3") (pin "55") (pinfunction "GPIO44/ADC4_55") (pintype "passive"))
      (node (ref "X1") (pin "45") (pinfunction "45_45") (pintype "passive"))
    )
    (net (code "53") (name "/GPIO45") (class "Default")
      (node (ref "U3") (pin "56") (pinfunction "GPIO45/ADC5_56") (pintype "passive"))
      (node (ref "X1") (pin "46") (pinfunction "46_46") (pintype "passive"))
    )
    (net (code "54") (name "/GPIO46") (class "Default")
      (node (ref "U3") (pin "57") (pinfunction "GPIO46/ADC6_57") (pintype "passive"))
      (node (ref "X1") (pin "47") (pinfunction "47_47") (pintype "passive"))
    )
    (net (code "55") (name "/GPIO47") (class "Default")
      (node (ref "U3") (pin "58") (pinfunction "GPIO47/ADC7_58") (pintype "passive"))
      (node (ref "X1") (pin "48") (pinfunction "48_48") (pintype "passive"))
    )
    (net (code "56") (name "/QSPI_CS") (class "Default")
      (node (ref "R4") (pin "1") (pinfunction "1_1") (pintype "passive"))
      (node (ref "R5") (pin "2") (pinfunction "2_2") (pintype "passive"))
      (node (ref "U2") (pin "1") (pinfunction "CSn_1") (pintype "passive"))
    )
    (net (code "57") (name "/QSPI_SCLK") (class "Default")
      (node (ref "U1") (pin "6") (pinfunction "CLK_6") (pintype "passive"))
      (node (ref "U2") (pin "6") (pinfunction "CLK_6") (pintype "passive"))
      (node (ref "U3") (pin "71") (pinfunction "QSPI_SCLK_71") (pintype "passive"))
    )
    (net (code "58") (name "/QSPI_SD0") (class "Default")
      (node (ref "U1") (pin "5") (pinfunction "DI/IO0_5") (pintype "passive"))
      (node (ref "U2") (pin "5") (pinfunction "DI/IO0_5") (pintype "passive"))
      (node (ref "U3") (pin "72") (pinfunction "QSPI_SD0_72") (pintype "passive"))
    )
    (net (code "59") (name "/QSPI_SD1") (class "Default")
      (node (ref "U1") (pin "2") (pinfunction "DO/IO1_2") (pintype "passive"))
      (node (ref "U2") (pin "2") (pinfunction "DO/IO1_2") (pintype "passive"))
      (node (ref "U3") (pin "74") (pinfunction "QSPI_SD1_74") (pintype "passive"))
    )
    (net (code "60") (name "/QSPI_SD2") (class "Default")
      (node (ref "U1") (pin "3") (pinfunction "WPn/IO2_3") (pintype "passive"))
      (node (ref "U2") (pin "3") (pinfunction "WPn/IO2_3") (pintype "passive"))
      (node (ref "U3") (pin "73") (pinfunction "QSPI_SD2_73") (pintype "passive"))
    )
    (net (code "61") (name "/QSPI_SD3") (class "Default")
      (node (ref "U1") (pin "7") (pinfunction "HOLDn/IO3_7") (pintype "passive"))
      (node (ref "U2") (pin "7") (pinfunction "HOLDn/IO3_7") (pintype "passive"))
      (node (ref "U3") (pin "70") (pinfunction "QSPI_SD3_70") (pintype "passive"))
    )
    (net (code "62") (name "/QSPI_SS") (class "Default")
      (node (ref "R6") (pin "2") (pinfunction "2_2") (pintype "passive"))
      (node (ref "U1") (pin "1") (pinfunction "CSn_1") (pintype "passive"))
      (node (ref "U3") (pin "75") (pinfunction "QSPI_SS_75") (pintype "passive"))
    )
    (net (code "63") (name "/RUN") (class "Default")
      (node (ref "R7") (pin "2") (pinfunction "2_2") (pintype "passive"))
      (node (ref "U3") (pin "35") (pinfunction "RUN_35") (pintype "passive"))
    )
    (net (code "64") (name "/SWCLK") (class "Default")
      (node (ref "U3") (pin "33") (pinfunction "SWSLK_33") (pintype "passive"))
      (node (ref "X8") (pin "1") (pinfunction "1_1") (pintype "passive"))
    )
    (net (code "65") (name "/SWDIO") (class "Default")
      (node (ref "U3") (pin "34") (pinfunction "SWDIO_34") (pintype "passive"))
      (node (ref "X8") (pin "3") (pinfunction "3_3") (pintype "passive"))
    )
    (net (code "66") (name "/XIN") (class "Default")
      (node (ref "C23") (pin "2") (pinfunction "2_2") (pintype "passive"))
      (node (ref "U3") (pin "30") (pinfunction "XIN_30") (pintype "passive"))
      (node (ref "Y1") (pin "1") (pinfunction "IN_1") (pintype "passive"))
    )
    (net (code "67") (name "/XOUT") (class "Default")
      (node (ref "R11") (pin "2") (pinfunction "2_2") (pintype "passive"))
      (node (ref "U3") (pin "31") (pinfunction "XOUT_31") (pintype "passive"))
    )
    (net (code "68") (name "GND") (class "Default")
      (node (ref "C1") (pin "1") (pinfunction "1_1") (pintype "passive"))
      (node (ref "C10") (pin "1") (pinfunction "1_1") (pintype "passive"))
      (node (ref "C11") (pin "1") (pinfunction "1_1") (pintype "passive"))
      (node (ref "C12") (pin "2") (pinfunction "2_2") (pintype "passive"))
      (node (ref "C13") (pin "1") (pinfunction "1_1") (pintype "passive"))
      (node (ref "C14") (pin "1") (pinfunction "1_1") (pintype "passive"))
      (node (ref "C15") (pin "2") (pinfunction "2_2") (pintype "passive"))
      (node (ref "C16") (pin "1") (pinfunction "1_1") (pintype "passive"))
      (node (ref "C18") (pin "1") (pinfunction "1_1") (pintype "passive"))
      (node (ref "C19") (pin "1") (pinfunction "1_1") (pintype "passive"))
      (node (ref "C2") (pin "1") (pinfunction "1_1") (pintype "passive"))
      (node (ref "C20") (pin "1") (pinfunction "1_1") (pintype "passive"))
      (node (ref "C21") (pin "1") (pinfunction "1_1") (pintype "passive"))
      (node (ref "C22") (pin "1") (pinfunction "1_1") (pintype "passive"))
      (node (ref "C23") (pin "1") (pinfunction "1_1") (pintype "passive"))
      (node (ref "C24") (pin "1") (pinfunction "1_1") (pintype "passive"))
      (node (ref "C25") (pin "2") (pinfunction "2_2") (pintype "passive"))
      (node (ref "C26") (pin "2") (pinfunction "2_2") (pintype "passive"))
      (node (ref "C3") (pin "1") (pinfunction "1_1") (pintype "passive"))
      (node (ref "C4") (pin "1") (pinfunction "1_1") (pintype "passive"))
      (node (ref "C5") (pin "1") (pinfunction "1_1") (pintype "passive"))
      (node (ref "C6") (pin "1") (pinfunction "1_1") (pintype "passive"))
      (node (ref "C7") (pin "1") (pinfunction "1_1") (pintype "passive"))
      (node (ref "C8") (pin "1") (pinfunction "1_1") (pintype "passive"))
      (node (ref "C9") (pin "1") (pinfunction "1_1") (pintype "passive"))
      (node (ref "D1") (pin "2") (pinfunction "Anode_2") (pintype "passive"))
      (node (ref "R5") (pin "1") (pinfunction "1_1") (pintype "passive"))
      (node (ref "SW1") (pin "1") (pinfunction "1_1") (pintype "passive"))
      (node (ref "SW1") (pin "2") (pinfunction "2_2") (pintype "passive"))
      (node (ref "SW2") (pin "1") (pinfunction "1_1") (pintype "passive"))
      (node (ref "SW2") (pin "2") (pinfunction "2_2") (pintype "passive"))
      (node (ref "U1") (pin "0") (pinfunction "EP_0") (pintype "passive"))
      (node (ref "U1") (pin "4") (pinfunction "GND_4") (pintype "passive"))
      (node (ref "U2") (pin "4") (pinfunction "VSS_4") (pintype "passive"))
      (node (ref "U3") (pin "0") (pinfunction "GND_0") (pintype "passive"))
      (node (ref "U3") (pin "62") (pinfunction "VREG_PGND_62") (pintype "passive"))
      (node (ref "U4") (pin "2") (pinfunction "GND_2") (pintype "passive"))
      (node (ref "U5") (pin "1") (pinfunction "GND_1") (pintype "passive"))
      (node (ref "X4") (pin "4") (pinfunction "4_4") (pintype "passive"))
      (node (ref "X6") (pin "1") (pinfunction "1_1") (pintype "passive"))
      (node (ref "X6") (pin "2") (pinfunction "2_2") (pintype "passive"))
      (node (ref "X6") (pin "3") (pinfunction "3_3") (pintype "passive"))
      (node (ref "X7") (pin "5") (pinfunction "5_5") (pintype "passive"))
      (node (ref "X7") (pin "6") (pinfunction "6_6") (pintype "passive"))
      (node (ref "X7") (pin "7") (pinfunction "7_7") (pintype "passive"))
      (node (ref "X7") (pin "8") (pinfunction "8_8") (pintype "passive"))
      (node (ref "X7") (pin "9") (pinfunction "9_9") (pintype "passive"))
      (node (ref "X8") (pin "2") (pinfunction "2_2") (pintype "passive"))
      (node (ref "Y1") (pin "2") (pinfunction "GND_2") (pintype "passive"))
      (node (ref "Y1") (pin "4") (pinfunction "GND_4") (pintype "passive"))
    )
    (net (code "69") (name "IOVDD") (class "Default")
      (node (ref "C10") (pin "2") (pinfunction "2_2") (pintype "passive"))
      (node (ref "C11") (pin "2") (pinfunction "2_2") (pintype "passive"))
      (node (ref "C4") (pin "2") (pinfunction "2_2") (pintype "passive"))
      (node (ref "C5") (pin "2") (pinfunction "2_2") (pintype "passive"))
      (node (ref "C6") (pin "2") (pinfunction "2_2") (pintype "passive"))
      (node (ref "C7") (pin "2") (pinfunction "2_2") (pintype "passive"))
      (node (ref "C8") (pin "2") (pinfunction "2_2") (pintype "passive"))
      (node (ref "C9") (pin "2") (pinfunction "2_2") (pintype "passive"))
      (node (ref "JP2") (pin "2") (pinfunction "2_2") (pintype "passive"))
      (node (ref "JP3") (pin "2") (pinfunction "2_2") (pintype "passive"))
      (node (ref "R1") (pin "2") (pinfunction "2_2") (pintype "passive"))
      (node (ref "U3") (pin "15") (pinfunction "IOVDD_15") (pintype "passive"))
      (node (ref "U3") (pin "24") (pinfunction "IOVDD_24") (pintype "passive"))
      (node (ref "U3") (pin "29") (pinfunction "IOVDD_29") (pintype "passive"))
      (node (ref "U3") (pin "41") (pinfunction "IOVDD_41") (pintype "passive"))
      (node (ref "U3") (pin "5") (pinfunction "IOVDD_5") (pintype "passive"))
      (node (ref "U3") (pin "50") (pinfunction "IOVDD_50") (pintype "passive"))
      (node (ref "U3") (pin "60") (pinfunction "IOVDD_60") (pintype "passive"))
      (node (ref "U3") (pin "76") (pinfunction "IOVDD_76") (pintype "passive"))
      (node (ref "X8") (pin "4") (pinfunction "4_4") (pintype "passive"))
    )
    (net (code "70") (name "Net-(D1-Cathode)") (class "Default")
      (node (ref "D1") (pin "1") (pinfunction "Cathode_1") (pintype "passive"))
      (node (ref "R10") (pin "1") (pinfunction "1_1") (pintype "passive"))
      (node (ref "U3") (pin "59") (pinfunction "ADC_AVDD_59") (pintype "passive"))
    )
    (net (code "71") (name "Net-(JP1-Pad2)") (class "Default")
      (node (ref "JP1") (pin "2") (pinfunction "2_2") (pintype "passive"))
      (node (ref "X1") (pin "1") (pinfunction "1_1") (pintype "passive"))
    )
    (net (code "72") (name "Net-(JP4-Pad1)") (class "Default")
      (node (ref "JP4") (pin "1") (pinfunction "1_1") (pintype "passive"))
      (node (ref "R1") (pin "1") (pinfunction "1_1") (pintype "passive"))
      (node (ref "R4") (pin "2") (pinfunction "2_2") (pintype "passive"))
    )
    (net (code "73") (name "Net-(R6-Pad1)") (class "Default")
      (node (ref "R6") (pin "1") (pinfunction "1_1") (pintype "passive"))
      (node (ref "SW1") (pin "3") (pinfunction "3_3") (pintype "passive"))
      (node (ref "SW1") (pin "4") (pinfunction "4_4") (pintype "passive"))
    )
    (net (code "74") (name "Net-(R7-Pad1)") (class "Default")
      (node (ref "R7") (pin "1") (pinfunction "1_1") (pintype "passive"))
      (node (ref "SW2") (pin "3") (pinfunction "3_3") (pintype "passive"))
      (node (ref "SW2") (pin "4") (pinfunction "4_4") (pintype "passive"))
    )
    (net (code "75") (name "Net-(U3-VREG_AVDD)") (class "Default")
      (node (ref "C14") (pin "2") (pinfunction "2_2") (pintype "passive"))
      (node (ref "R3") (pin "2") (pinfunction "2_2") (pintype "passive"))
      (node (ref "U3") (pin "61") (pinfunction "VREG_AVDD_61") (pintype "passive"))
    )
    (net (code "76") (name "Net-(U3-VREG_LX)") (class "Default")
      (node (ref "L1") (pin "2") (pinfunction "2_2") (pintype "passive"))
      (node (ref "U3") (pin "63") (pinfunction "VREG_LX_63") (pintype "passive"))
    )
    (net (code "77") (name "Net-(Y1-OUT)") (class "Default")
      (node (ref "C24") (pin "2") (pinfunction "2_2") (pintype "passive"))
      (node (ref "R11") (pin "1") (pinfunction "1_1") (pintype "passive"))
      (node (ref "Y1") (pin "3") (pinfunction "OUT_3") (pintype "passive"))
    )
    (net (code "78") (name "VBUS") (class "Default")
      (node (ref "C21") (pin "2") (pinfunction "2_2") (pintype "passive"))
      (node (ref "C25") (pin "1") (pinfunction "1_1") (pintype "passive"))
      (node (ref "U4") (pin "1") (pinfunction "Vin_1") (pintype "passive"))
      (node (ref "U4") (pin "3") (pinfunction "Shutdown_3") (pintype "passive"))
      (node (ref "U5") (pin "3") (pinfunction "Vin_3") (pintype "passive"))
      (node (ref "X2") (pin "1") (pinfunction "1_1") (pintype "passive"))
      (node (ref "X2") (pin "2") (pinfunction "2_2") (pintype "passive"))
      (node (ref "X2") (pin "3") (pinfunction "3_3") (pintype "passive"))
      (node (ref "X4") (pin "1") (pinfunction "1_1") (pintype "passive"))
      (node (ref "X7") (pin "1") (pinfunction "1_1") (pintype "passive"))
    )
    (net (code "79") (name "unconnected-(X7-Pad4)") (class "Default")
      (node (ref "X7") (pin "4") (pinfunction "4_4") (pintype "passive+no_connect"))
    )
  )
)
